# ORAO2007.net
KiCad netlist of a schematic drawn in EAGLE
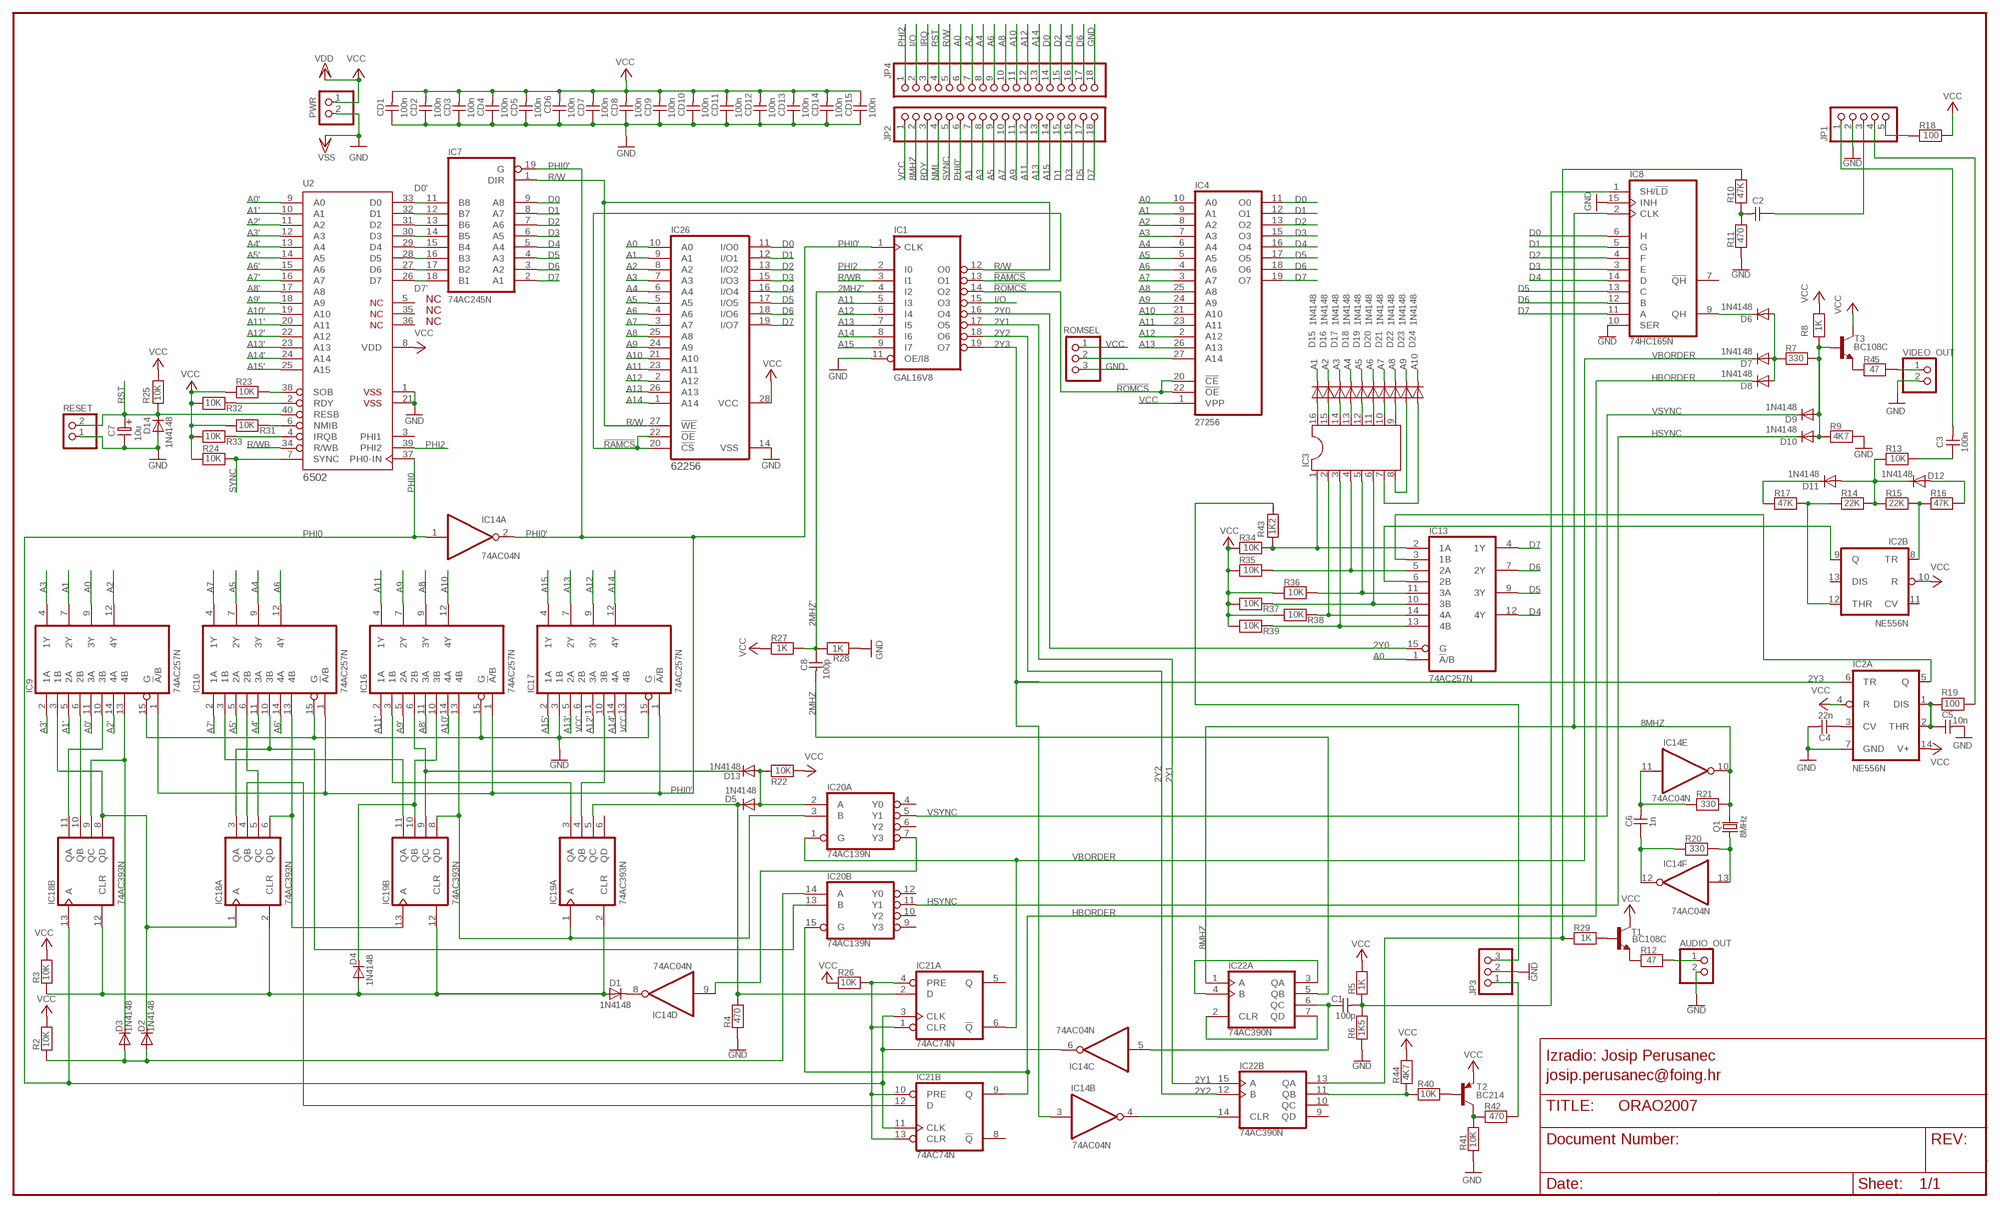
[diagram p0: schematic, sheet 1]

(export (version "E")
  (design (tool "Eeschema 10.0.6"))
  (components
    (comp (ref "AUDIO_OUT")
      (value "PINHD-1X2")
      (footprint "eagle-import:1X02")
      (libsource (lib "eagle-import") (part "PINHD-1X2"))
    )
    (comp (ref "C1")
      (value "100p")
      (footprint "eagle-import:C-5")
      (libsource (lib "eagle-import") (part "CAPNP-5"))
    )
    (comp (ref "C2")
      (value "CAPNP-5")
      (footprint "eagle-import:C-5")
      (libsource (lib "eagle-import") (part "CAPNP-5"))
    )
    (comp (ref "C3")
      (value "100n")
      (footprint "eagle-import:C-5")
      (libsource (lib "eagle-import") (part "CAPNP-5"))
    )
    (comp (ref "C4")
      (value "22n")
      (footprint "eagle-import:C-5")
      (libsource (lib "eagle-import") (part "CAPNP-5"))
    )
    (comp (ref "C5")
      (value "10n")
      (footprint "eagle-import:C-5")
      (libsource (lib "eagle-import") (part "CAPNP-5"))
    )
    (comp (ref "C6")
      (value "1n")
      (footprint "eagle-import:C-5")
      (libsource (lib "eagle-import") (part "CAPNP-5"))
    )
    (comp (ref "C7")
      (value "10u")
      (footprint "eagle-import:ES-2,5L")
      (libsource (lib "eagle-import") (part "ELC-2,5L"))
    )
    (comp (ref "C8")
      (value "100p")
      (footprint "eagle-import:C-5")
      (libsource (lib "eagle-import") (part "CAPNP-5"))
    )
    (comp (ref "CD1")
      (value "100n")
      (footprint "eagle-import:C-5")
      (libsource (lib "eagle-import") (part "CAPNP-5"))
    )
    (comp (ref "CD2")
      (value "100n")
      (footprint "eagle-import:C-5")
      (libsource (lib "eagle-import") (part "CAPNP-5"))
    )
    (comp (ref "CD3")
      (value "100n")
      (footprint "eagle-import:C-5")
      (libsource (lib "eagle-import") (part "CAPNP-5"))
    )
    (comp (ref "CD4")
      (value "100n")
      (footprint "eagle-import:C-5")
      (libsource (lib "eagle-import") (part "CAPNP-5"))
    )
    (comp (ref "CD5")
      (value "100n")
      (footprint "eagle-import:C-5")
      (libsource (lib "eagle-import") (part "CAPNP-5"))
    )
    (comp (ref "CD6")
      (value "100n")
      (footprint "eagle-import:C-5")
      (libsource (lib "eagle-import") (part "CAPNP-5"))
    )
    (comp (ref "CD7")
      (value "100n")
      (footprint "eagle-import:C-5")
      (libsource (lib "eagle-import") (part "CAPNP-5"))
    )
    (comp (ref "CD8")
      (value "100n")
      (footprint "eagle-import:C-5")
      (libsource (lib "eagle-import") (part "CAPNP-5"))
    )
    (comp (ref "CD9")
      (value "100n")
      (footprint "eagle-import:C-5")
      (libsource (lib "eagle-import") (part "CAPNP-5"))
    )
    (comp (ref "CD10")
      (value "100n")
      (footprint "eagle-import:C-5")
      (libsource (lib "eagle-import") (part "CAPNP-5"))
    )
    (comp (ref "CD11")
      (value "100n")
      (footprint "eagle-import:C-5")
      (libsource (lib "eagle-import") (part "CAPNP-5"))
    )
    (comp (ref "CD12")
      (value "100n")
      (footprint "eagle-import:C-5")
      (libsource (lib "eagle-import") (part "CAPNP-5"))
    )
    (comp (ref "CD13")
      (value "100n")
      (footprint "eagle-import:C-5")
      (libsource (lib "eagle-import") (part "CAPNP-5"))
    )
    (comp (ref "CD14")
      (value "100n")
      (footprint "eagle-import:C-5")
      (libsource (lib "eagle-import") (part "CAPNP-5"))
    )
    (comp (ref "CD15")
      (value "100n")
      (footprint "eagle-import:C-5")
      (libsource (lib "eagle-import") (part "CAPNP-5"))
    )
    (comp (ref "D1")
      (value "1N4148")
      (footprint "eagle-import:DO35-10")
      (libsource (lib "eagle-import") (part "1N4148"))
    )
    (comp (ref "D2")
      (value "1N4148")
      (footprint "eagle-import:DO35-10")
      (libsource (lib "eagle-import") (part "1N4148"))
    )
    (comp (ref "D3")
      (value "1N4148")
      (footprint "eagle-import:DO35-10")
      (libsource (lib "eagle-import") (part "1N4148"))
    )
    (comp (ref "D4")
      (value "1N4148")
      (footprint "eagle-import:DO35-10")
      (libsource (lib "eagle-import") (part "1N4148"))
    )
    (comp (ref "D5")
      (value "1N4148")
      (footprint "eagle-import:DO35-10")
      (libsource (lib "eagle-import") (part "1N4148"))
    )
    (comp (ref "D6")
      (value "1N4148")
      (footprint "eagle-import:DO35-10")
      (libsource (lib "eagle-import") (part "1N4148"))
    )
    (comp (ref "D7")
      (value "1N4148")
      (footprint "eagle-import:DO35-10")
      (libsource (lib "eagle-import") (part "1N4148"))
    )
    (comp (ref "D8")
      (value "1N4148")
      (footprint "eagle-import:DO35-10")
      (libsource (lib "eagle-import") (part "1N4148"))
    )
    (comp (ref "D9")
      (value "1N4148")
      (footprint "eagle-import:DO35-10")
      (libsource (lib "eagle-import") (part "1N4148"))
    )
    (comp (ref "D10")
      (value "1N4148")
      (footprint "eagle-import:DO35-10")
      (libsource (lib "eagle-import") (part "1N4148"))
    )
    (comp (ref "D11")
      (value "1N4148")
      (footprint "eagle-import:DO35-10")
      (libsource (lib "eagle-import") (part "1N4148"))
    )
    (comp (ref "D12")
      (value "1N4148")
      (footprint "eagle-import:DO35-10")
      (libsource (lib "eagle-import") (part "1N4148"))
    )
    (comp (ref "D13")
      (value "1N4148")
      (footprint "eagle-import:DO35-10")
      (libsource (lib "eagle-import") (part "1N4148"))
    )
    (comp (ref "D14")
      (value "1N4148")
      (footprint "eagle-import:DO35-10")
      (libsource (lib "eagle-import") (part "1N4148"))
    )
    (comp (ref "D15")
      (value "1N4148")
      (footprint "eagle-import:DO35-10")
      (libsource (lib "eagle-import") (part "1N4148"))
    )
    (comp (ref "D16")
      (value "1N4148")
      (footprint "eagle-import:DO35-10")
      (libsource (lib "eagle-import") (part "1N4148"))
    )
    (comp (ref "D17")
      (value "1N4148")
      (footprint "eagle-import:DO35-10")
      (libsource (lib "eagle-import") (part "1N4148"))
    )
    (comp (ref "D18")
      (value "1N4148")
      (footprint "eagle-import:DO35-10")
      (libsource (lib "eagle-import") (part "1N4148"))
    )
    (comp (ref "D19")
      (value "1N4148")
      (footprint "eagle-import:DO35-10")
      (libsource (lib "eagle-import") (part "1N4148"))
    )
    (comp (ref "D20")
      (value "1N4148")
      (footprint "eagle-import:DO35-10")
      (libsource (lib "eagle-import") (part "1N4148"))
    )
    (comp (ref "D21")
      (value "1N4148")
      (footprint "eagle-import:DO35-10")
      (libsource (lib "eagle-import") (part "1N4148"))
    )
    (comp (ref "D22")
      (value "1N4148")
      (footprint "eagle-import:DO35-10")
      (libsource (lib "eagle-import") (part "1N4148"))
    )
    (comp (ref "D23")
      (value "1N4148")
      (footprint "eagle-import:DO35-10")
      (libsource (lib "eagle-import") (part "1N4148"))
    )
    (comp (ref "D24")
      (value "1N4148")
      (footprint "eagle-import:DO35-10")
      (libsource (lib "eagle-import") (part "1N4148"))
    )
    (comp (ref "IC1")
      (value "GAL16V8")
      (footprint "eagle-import:DIL20")
      (libsource (lib "eagle-import") (part "16V8"))
    )
    (comp (ref "IC2")
      (value "NE556N")
      (footprint "eagle-import:DIL14")
      (libsource (lib "eagle-import") (part "556NNE"))
    )
    (comp (ref "IC3")
      (value "DIL16S")
      (footprint "eagle-import:SOCKED-16")
      (libsource (lib "eagle-import") (part "DIL16S"))
    )
    (comp (ref "IC4")
      (value "27256")
      (footprint "eagle-import:DIL28")
      (libsource (lib "eagle-import") (part "27256"))
    )
    (comp (ref "IC7")
      (value "74AC245N")
      (footprint "eagle-import:DIL20")
      (libsource (lib "eagle-import") (part "74245NAC"))
    )
    (comp (ref "IC8")
      (value "74HC165N")
      (footprint "eagle-import:DIL16")
      (libsource (lib "eagle-import") (part "74165NHC"))
    )
    (comp (ref "IC9")
      (value "74AC257N")
      (footprint "eagle-import:DIL16")
      (libsource (lib "eagle-import") (part "74257NAC"))
    )
    (comp (ref "IC10")
      (value "74AC257N")
      (footprint "eagle-import:DIL16")
      (libsource (lib "eagle-import") (part "74257NAC"))
    )
    (comp (ref "IC13")
      (value "74AC257N")
      (footprint "eagle-import:DIL16")
      (libsource (lib "eagle-import") (part "74257NAC"))
    )
    (comp (ref "IC14")
      (value "74AC04N")
      (footprint "eagle-import:DIL14")
      (libsource (lib "eagle-import") (part "7404NAC"))
    )
    (comp (ref "IC16")
      (value "74AC257N")
      (footprint "eagle-import:DIL16")
      (libsource (lib "eagle-import") (part "74257NAC"))
    )
    (comp (ref "IC17")
      (value "74AC257N")
      (footprint "eagle-import:DIL16")
      (libsource (lib "eagle-import") (part "74257NAC"))
    )
    (comp (ref "IC18")
      (value "74AC393N")
      (footprint "eagle-import:DIL14")
      (libsource (lib "eagle-import") (part "74393NAC"))
    )
    (comp (ref "IC19")
      (value "74AC393N")
      (footprint "eagle-import:DIL14")
      (libsource (lib "eagle-import") (part "74393NAC"))
    )
    (comp (ref "IC20")
      (value "74AC139N")
      (footprint "eagle-import:DIL16")
      (libsource (lib "eagle-import") (part "74139NAC"))
    )
    (comp (ref "IC21")
      (value "74AC74N")
      (footprint "eagle-import:DIL14")
      (libsource (lib "eagle-import") (part "7474NAC"))
    )
    (comp (ref "IC22")
      (value "74AC390N")
      (footprint "eagle-import:DIL16")
      (libsource (lib "eagle-import") (part "74390NAC"))
    )
    (comp (ref "IC26")
      (value "62256")
      (footprint "eagle-import:DIL28-6")
      (libsource (lib "eagle-import") (part "62256P"))
    )
    (comp (ref "JP1")
      (value "PINHD-1X5")
      (footprint "eagle-import:1X05")
      (libsource (lib "eagle-import") (part "PINHD-1X5"))
    )
    (comp (ref "JP2")
      (value "PINHD-1X18")
      (footprint "eagle-import:1X18")
      (libsource (lib "eagle-import") (part "PINHD-1X18"))
    )
    (comp (ref "JP3")
      (value "PINHD-1X3")
      (footprint "eagle-import:1X03")
      (libsource (lib "eagle-import") (part "PINHD-1X3"))
    )
    (comp (ref "JP4")
      (value "PINHD-1X18")
      (footprint "eagle-import:1X18")
      (libsource (lib "eagle-import") (part "PINHD-1X18"))
    )
    (comp (ref "PWR")
      (value "PINHD-1X2")
      (footprint "eagle-import:1X02")
      (libsource (lib "eagle-import") (part "PINHD-1X2"))
    )
    (comp (ref "Q1")
      (value "8MHz")
      (footprint "eagle-import:HC49_S")
      (libsource (lib "eagle-import") (part "CRYTALHC49S"))
    )
    (comp (ref "R2")
      (value "10K")
      (footprint "eagle-import:R-7,5")
      (libsource (lib "eagle-import") (part "RESEU-7,5"))
    )
    (comp (ref "R3")
      (value "10K")
      (footprint "eagle-import:R-7,5")
      (libsource (lib "eagle-import") (part "RESEU-7,5"))
    )
    (comp (ref "R4")
      (value "470")
      (footprint "eagle-import:R-7,5")
      (libsource (lib "eagle-import") (part "RESEU-7,5"))
    )
    (comp (ref "R5")
      (value "1K")
      (footprint "eagle-import:R-7,5")
      (libsource (lib "eagle-import") (part "RESEU-7,5"))
    )
    (comp (ref "R6")
      (value "1K5")
      (footprint "eagle-import:R-7,5")
      (libsource (lib "eagle-import") (part "RESEU-7,5"))
    )
    (comp (ref "R7")
      (value "330")
      (footprint "eagle-import:R-7,5")
      (libsource (lib "eagle-import") (part "RESEU-7,5"))
    )
    (comp (ref "R8")
      (value "1K")
      (footprint "eagle-import:R-7,5")
      (libsource (lib "eagle-import") (part "RESEU-7,5"))
    )
    (comp (ref "R9")
      (value "4K7")
      (footprint "eagle-import:R-7,5")
      (libsource (lib "eagle-import") (part "RESEU-7,5"))
    )
    (comp (ref "R10")
      (value "47K")
      (footprint "eagle-import:R-7,5")
      (libsource (lib "eagle-import") (part "RESEU-7,5"))
    )
    (comp (ref "R11")
      (value "470")
      (footprint "eagle-import:R-7,5")
      (libsource (lib "eagle-import") (part "RESEU-7,5"))
    )
    (comp (ref "R12")
      (value "47")
      (footprint "eagle-import:R-7,5")
      (libsource (lib "eagle-import") (part "RESEU-7,5"))
    )
    (comp (ref "R13")
      (value "10K")
      (footprint "eagle-import:R-7,5")
      (libsource (lib "eagle-import") (part "RESEU-7,5"))
    )
    (comp (ref "R14")
      (value "22K")
      (footprint "eagle-import:R-7,5")
      (libsource (lib "eagle-import") (part "RESEU-7,5"))
    )
    (comp (ref "R15")
      (value "22K")
      (footprint "eagle-import:R-7,5")
      (libsource (lib "eagle-import") (part "RESEU-7,5"))
    )
    (comp (ref "R16")
      (value "47K")
      (footprint "eagle-import:R-7,5")
      (libsource (lib "eagle-import") (part "RESEU-7,5"))
    )
    (comp (ref "R17")
      (value "47K")
      (footprint "eagle-import:R-7,5")
      (libsource (lib "eagle-import") (part "RESEU-7,5"))
    )
    (comp (ref "R18")
      (value "100")
      (footprint "eagle-import:R-7,5")
      (libsource (lib "eagle-import") (part "RESEU-7,5"))
    )
    (comp (ref "R19")
      (value "100")
      (footprint "eagle-import:R-7,5")
      (libsource (lib "eagle-import") (part "RESEU-7,5"))
    )
    (comp (ref "R20")
      (value "330")
      (footprint "eagle-import:R-7,5")
      (libsource (lib "eagle-import") (part "RESEU-7,5"))
    )
    (comp (ref "R21")
      (value "330")
      (footprint "eagle-import:R-7,5")
      (libsource (lib "eagle-import") (part "RESEU-7,5"))
    )
    (comp (ref "R22")
      (value "10K")
      (footprint "eagle-import:R-7,5")
      (libsource (lib "eagle-import") (part "RESEU-7,5"))
    )
    (comp (ref "R23")
      (value "10K")
      (footprint "eagle-import:R-7,5")
      (libsource (lib "eagle-import") (part "RESEU-7,5"))
    )
    (comp (ref "R24")
      (value "10K")
      (footprint "eagle-import:R-7,5")
      (libsource (lib "eagle-import") (part "RESEU-7,5"))
    )
    (comp (ref "R25")
      (value "10K")
      (footprint "eagle-import:R-7,5")
      (libsource (lib "eagle-import") (part "RESEU-7,5"))
    )
    (comp (ref "R26")
      (value "10K")
      (footprint "eagle-import:R-7,5")
      (libsource (lib "eagle-import") (part "RESEU-7,5"))
    )
    (comp (ref "R27")
      (value "1K")
      (footprint "eagle-import:R-7,5")
      (libsource (lib "eagle-import") (part "RESEU-7,5"))
    )
    (comp (ref "R28")
      (value "1K")
      (footprint "eagle-import:R-7,5")
      (libsource (lib "eagle-import") (part "RESEU-7,5"))
    )
    (comp (ref "R29")
      (value "1K")
      (footprint "eagle-import:R-7,5")
      (libsource (lib "eagle-import") (part "RESEU-7,5"))
    )
    (comp (ref "R31")
      (value "10K")
      (footprint "eagle-import:R-7,5")
      (libsource (lib "eagle-import") (part "RESEU-7,5"))
    )
    (comp (ref "R32")
      (value "10K")
      (footprint "eagle-import:R-7,5")
      (libsource (lib "eagle-import") (part "RESEU-7,5"))
    )
    (comp (ref "R33")
      (value "10K")
      (footprint "eagle-import:R-7,5")
      (libsource (lib "eagle-import") (part "RESEU-7,5"))
    )
    (comp (ref "R34")
      (value "10K")
      (footprint "eagle-import:R-7,5")
      (libsource (lib "eagle-import") (part "RESEU-7,5"))
    )
    (comp (ref "R35")
      (value "10K")
      (footprint "eagle-import:R-7,5")
      (libsource (lib "eagle-import") (part "RESEU-7,5"))
    )
    (comp (ref "R36")
      (value "10K")
      (footprint "eagle-import:R-7,5")
      (libsource (lib "eagle-import") (part "RESEU-7,5"))
    )
    (comp (ref "R37")
      (value "10K")
      (footprint "eagle-import:R-7,5")
      (libsource (lib "eagle-import") (part "RESEU-7,5"))
    )
    (comp (ref "R38")
      (value "10K")
      (footprint "eagle-import:R-7,5")
      (libsource (lib "eagle-import") (part "RESEU-7,5"))
    )
    (comp (ref "R39")
      (value "10K")
      (footprint "eagle-import:R-7,5")
      (libsource (lib "eagle-import") (part "RESEU-7,5"))
    )
    (comp (ref "R40")
      (value "10K")
      (footprint "eagle-import:R-7,5")
      (libsource (lib "eagle-import") (part "RESEU-7,5"))
    )
    (comp (ref "R41")
      (value "10K")
      (footprint "eagle-import:R-7,5")
      (libsource (lib "eagle-import") (part "RESEU-7,5"))
    )
    (comp (ref "R42")
      (value "470")
      (footprint "eagle-import:R-7,5")
      (libsource (lib "eagle-import") (part "RESEU-7,5"))
    )
    (comp (ref "R43")
      (value "1K2")
      (footprint "eagle-import:R-7,5")
      (libsource (lib "eagle-import") (part "RESEU-7,5"))
    )
    (comp (ref "R44")
      (value "4K7")
      (footprint "eagle-import:R-7,5")
      (libsource (lib "eagle-import") (part "RESEU-7,5"))
    )
    (comp (ref "R45")
      (value "47")
      (footprint "eagle-import:R-7,5")
      (libsource (lib "eagle-import") (part "RESEU-7,5"))
    )
    (comp (ref "RESET")
      (value "PINHD-1X2")
      (footprint "eagle-import:1X02")
      (libsource (lib "eagle-import") (part "PINHD-1X2"))
    )
    (comp (ref "ROMSEL")
      (value "PINHD-1X3")
      (footprint "eagle-import:1X03")
      (libsource (lib "eagle-import") (part "PINHD-1X3"))
    )
    (comp (ref "T1")
      (value "BC108C")
      (footprint "eagle-import:TO18")
      (libsource (lib "eagle-import") (part "BC108C"))
    )
    (comp (ref "T2")
      (value "BC214")
      (footprint "eagle-import:TO92")
      (libsource (lib "eagle-import") (part "BC214"))
    )
    (comp (ref "T3")
      (value "BC108C")
      (footprint "eagle-import:TO18")
      (libsource (lib "eagle-import") (part "BC108C"))
    )
    (comp (ref "U2")
      (value "6502")
      (footprint "eagle-import:DIP-40")
      (libsource (lib "eagle-import") (part "G65SC02P"))
    )
    (comp (ref "VIDEO_OUT")
      (value "PINHD-1X2")
      (footprint "eagle-import:1X02")
      (libsource (lib "eagle-import") (part "PINHD-1X2"))
    )
  )
  (nets
    (net (code "1") (name "/2MHZ") (class "Default")
      (node (ref "C8") (pin "2") (pinfunction "2_2") (pintype "passive"))
      (node (ref "IC22") (pin "5") (pinfunction "QB_5") (pintype "output"))
    )
    (net (code "2") (name "/2MHZ'") (class "Default")
      (node (ref "C8") (pin "1") (pinfunction "1_1") (pintype "passive"))
      (node (ref "IC1") (pin "4") (pinfunction "I2_4") (pintype "input"))
      (node (ref "R27") (pin "1") (pinfunction "1_1") (pintype "passive"))
      (node (ref "R28") (pin "2") (pinfunction "2_2") (pintype "passive"))
    )
    (net (code "3") (name "/2Y0") (class "Default")
      (node (ref "IC1") (pin "16") (pinfunction "O4_16") (pintype "bidirectional"))
      (node (ref "IC13") (pin "15") (pinfunction "G_15") (pintype "input"))
    )
    (net (code "4") (name "/2Y1") (class "Default")
      (node (ref "IC1") (pin "17") (pinfunction "O5_17") (pintype "bidirectional"))
      (node (ref "IC22") (pin "15") (pinfunction "A_15") (pintype "input"))
    )
    (net (code "5") (name "/2Y2") (class "Default")
      (node (ref "IC1") (pin "18") (pinfunction "O6_18") (pintype "bidirectional"))
      (node (ref "IC22") (pin "12") (pinfunction "B_12") (pintype "input"))
    )
    (net (code "6") (name "/2Y3") (class "Default")
      (node (ref "IC1") (pin "19") (pinfunction "O7_19") (pintype "bidirectional"))
      (node (ref "IC14") (pin "3") (pinfunction "I_3") (pintype "input"))
      (node (ref "IC2") (pin "6") (pinfunction "TR_6") (pintype "input"))
    )
    (net (code "7") (name "/8MHZ") (class "Default")
      (node (ref "IC14") (pin "10") (pinfunction "O_10") (pintype "output"))
      (node (ref "IC22") (pin "1") (pinfunction "A_1") (pintype "input"))
      (node (ref "IC8") (pin "2") (pinfunction "CLK_2") (pintype "input"))
      (node (ref "JP2") (pin "2") (pinfunction "2_2") (pintype "passive"))
      (node (ref "Q1") (pin "2") (pinfunction "2_2") (pintype "passive"))
      (node (ref "R21") (pin "2") (pinfunction "2_2") (pintype "passive"))
    )
    (net (code "8") (name "/A0") (class "Default")
      (node (ref "IC13") (pin "1") (pinfunction "~{A}/B_1") (pintype "input"))
      (node (ref "IC26") (pin "10") (pinfunction "A0_10") (pintype "input"))
      (node (ref "IC4") (pin "10") (pinfunction "A0_10") (pintype "input"))
      (node (ref "IC9") (pin "9") (pinfunction "3Y_9") (pintype "tri_state"))
      (node (ref "JP4") (pin "6") (pinfunction "6_6") (pintype "passive"))
    )
    (net (code "9") (name "/A0'") (class "Default")
      (node (ref "IC9") (pin "11") (pinfunction "3A_11") (pintype "input"))
      (node (ref "U2") (pin "9") (pinfunction "A0_9") (pintype "bidirectional"))
    )
    (net (code "10") (name "/A1") (class "Default")
      (node (ref "D15") (pin "C") (pinfunction "C_C") (pintype "passive"))
      (node (ref "IC26") (pin "9") (pinfunction "A1_9") (pintype "input"))
      (node (ref "IC4") (pin "9") (pinfunction "A1_9") (pintype "input"))
      (node (ref "IC9") (pin "7") (pinfunction "2Y_7") (pintype "tri_state"))
      (node (ref "JP2") (pin "7") (pinfunction "7_7") (pintype "passive"))
    )
    (net (code "11") (name "/A1'") (class "Default")
      (node (ref "IC9") (pin "5") (pinfunction "2A_5") (pintype "input"))
      (node (ref "U2") (pin "10") (pinfunction "A1_10") (pintype "bidirectional"))
    )
    (net (code "12") (name "/A2") (class "Default")
      (node (ref "D16") (pin "C") (pinfunction "C_C") (pintype "passive"))
      (node (ref "IC26") (pin "8") (pinfunction "A2_8") (pintype "input"))
      (node (ref "IC4") (pin "8") (pinfunction "A2_8") (pintype "input"))
      (node (ref "IC9") (pin "12") (pinfunction "4Y_12") (pintype "tri_state"))
      (node (ref "JP4") (pin "7") (pinfunction "7_7") (pintype "passive"))
    )
    (net (code "13") (name "/A2'") (class "Default")
      (node (ref "IC9") (pin "14") (pinfunction "4A_14") (pintype "input"))
      (node (ref "U2") (pin "11") (pinfunction "A2_11") (pintype "bidirectional"))
    )
    (net (code "14") (name "/A3") (class "Default")
      (node (ref "D17") (pin "C") (pinfunction "C_C") (pintype "passive"))
      (node (ref "IC26") (pin "7") (pinfunction "A3_7") (pintype "input"))
      (node (ref "IC4") (pin "7") (pinfunction "A3_7") (pintype "input"))
      (node (ref "IC9") (pin "4") (pinfunction "1Y_4") (pintype "tri_state"))
      (node (ref "JP2") (pin "8") (pinfunction "8_8") (pintype "passive"))
    )
    (net (code "15") (name "/A3'") (class "Default")
      (node (ref "IC9") (pin "2") (pinfunction "1A_2") (pintype "input"))
      (node (ref "U2") (pin "12") (pinfunction "A3_12") (pintype "bidirectional"))
    )
    (net (code "16") (name "/A4") (class "Default")
      (node (ref "D18") (pin "C") (pinfunction "C_C") (pintype "passive"))
      (node (ref "IC10") (pin "9") (pinfunction "3Y_9") (pintype "tri_state"))
      (node (ref "IC26") (pin "6") (pinfunction "A4_6") (pintype "input"))
      (node (ref "IC4") (pin "6") (pinfunction "A4_6") (pintype "input"))
      (node (ref "JP4") (pin "8") (pinfunction "8_8") (pintype "passive"))
    )
    (net (code "17") (name "/A4'") (class "Default")
      (node (ref "IC10") (pin "11") (pinfunction "3A_11") (pintype "input"))
      (node (ref "U2") (pin "13") (pinfunction "A4_13") (pintype "bidirectional"))
    )
    (net (code "18") (name "/A5") (class "Default")
      (node (ref "D19") (pin "C") (pinfunction "C_C") (pintype "passive"))
      (node (ref "IC10") (pin "7") (pinfunction "2Y_7") (pintype "tri_state"))
      (node (ref "IC26") (pin "5") (pinfunction "A5_5") (pintype "input"))
      (node (ref "IC4") (pin "5") (pinfunction "A5_5") (pintype "input"))
      (node (ref "JP2") (pin "9") (pinfunction "9_9") (pintype "passive"))
    )
    (net (code "19") (name "/A5'") (class "Default")
      (node (ref "IC10") (pin "5") (pinfunction "2A_5") (pintype "input"))
      (node (ref "U2") (pin "14") (pinfunction "A5_14") (pintype "bidirectional"))
    )
    (net (code "20") (name "/A6") (class "Default")
      (node (ref "D20") (pin "C") (pinfunction "C_C") (pintype "passive"))
      (node (ref "IC10") (pin "12") (pinfunction "4Y_12") (pintype "tri_state"))
      (node (ref "IC26") (pin "4") (pinfunction "A6_4") (pintype "input"))
      (node (ref "IC4") (pin "4") (pinfunction "A6_4") (pintype "input"))
      (node (ref "JP4") (pin "9") (pinfunction "9_9") (pintype "passive"))
    )
    (net (code "21") (name "/A6'") (class "Default")
      (node (ref "IC10") (pin "14") (pinfunction "4A_14") (pintype "input"))
      (node (ref "U2") (pin "15") (pinfunction "A6_15") (pintype "bidirectional"))
    )
    (net (code "22") (name "/A7") (class "Default")
      (node (ref "D21") (pin "C") (pinfunction "C_C") (pintype "passive"))
      (node (ref "IC10") (pin "4") (pinfunction "1Y_4") (pintype "tri_state"))
      (node (ref "IC26") (pin "3") (pinfunction "A7_3") (pintype "input"))
      (node (ref "IC4") (pin "3") (pinfunction "A7_3") (pintype "input"))
      (node (ref "JP2") (pin "10") (pinfunction "10_10") (pintype "passive"))
    )
    (net (code "23") (name "/A7'") (class "Default")
      (node (ref "IC10") (pin "2") (pinfunction "1A_2") (pintype "input"))
      (node (ref "U2") (pin "16") (pinfunction "A7_16") (pintype "bidirectional"))
    )
    (net (code "24") (name "/A8") (class "Default")
      (node (ref "D22") (pin "C") (pinfunction "C_C") (pintype "passive"))
      (node (ref "IC16") (pin "9") (pinfunction "3Y_9") (pintype "tri_state"))
      (node (ref "IC26") (pin "25") (pinfunction "A8_25") (pintype "input"))
      (node (ref "IC4") (pin "25") (pinfunction "A8_25") (pintype "input"))
      (node (ref "JP4") (pin "10") (pinfunction "10_10") (pintype "passive"))
    )
    (net (code "25") (name "/A8'") (class "Default")
      (node (ref "IC16") (pin "11") (pinfunction "3A_11") (pintype "input"))
      (node (ref "U2") (pin "17") (pinfunction "A8_17") (pintype "bidirectional"))
    )
    (net (code "26") (name "/A9") (class "Default")
      (node (ref "D23") (pin "C") (pinfunction "C_C") (pintype "passive"))
      (node (ref "IC16") (pin "7") (pinfunction "2Y_7") (pintype "tri_state"))
      (node (ref "IC26") (pin "24") (pinfunction "A9_24") (pintype "input"))
      (node (ref "IC4") (pin "24") (pinfunction "A9_24") (pintype "input"))
      (node (ref "JP2") (pin "11") (pinfunction "11_11") (pintype "passive"))
    )
    (net (code "27") (name "/A9'") (class "Default")
      (node (ref "IC16") (pin "5") (pinfunction "2A_5") (pintype "input"))
      (node (ref "U2") (pin "18") (pinfunction "A9_18") (pintype "bidirectional"))
    )
    (net (code "28") (name "/A10") (class "Default")
      (node (ref "D24") (pin "C") (pinfunction "C_C") (pintype "passive"))
      (node (ref "IC16") (pin "12") (pinfunction "4Y_12") (pintype "tri_state"))
      (node (ref "IC26") (pin "21") (pinfunction "A10_21") (pintype "input"))
      (node (ref "IC4") (pin "21") (pinfunction "A10_21") (pintype "input"))
      (node (ref "JP4") (pin "11") (pinfunction "11_11") (pintype "passive"))
    )
    (net (code "29") (name "/A10'") (class "Default")
      (node (ref "IC16") (pin "14") (pinfunction "4A_14") (pintype "input"))
      (node (ref "U2") (pin "19") (pinfunction "A10_19") (pintype "bidirectional"))
    )
    (net (code "30") (name "/A11") (class "Default")
      (node (ref "IC1") (pin "5") (pinfunction "I3_5") (pintype "input"))
      (node (ref "IC16") (pin "4") (pinfunction "1Y_4") (pintype "tri_state"))
      (node (ref "IC26") (pin "23") (pinfunction "A11_23") (pintype "input"))
      (node (ref "IC4") (pin "23") (pinfunction "A11_23") (pintype "input"))
      (node (ref "JP2") (pin "12") (pinfunction "12_12") (pintype "passive"))
    )
    (net (code "31") (name "/A11'") (class "Default")
      (node (ref "IC16") (pin "2") (pinfunction "1A_2") (pintype "input"))
      (node (ref "U2") (pin "20") (pinfunction "A11_20") (pintype "bidirectional"))
    )
    (net (code "32") (name "/A12") (class "Default")
      (node (ref "IC1") (pin "6") (pinfunction "I4_6") (pintype "input"))
      (node (ref "IC17") (pin "9") (pinfunction "3Y_9") (pintype "tri_state"))
      (node (ref "IC26") (pin "2") (pinfunction "A12_2") (pintype "input"))
      (node (ref "IC4") (pin "2") (pinfunction "A12_2") (pintype "input"))
      (node (ref "JP4") (pin "12") (pinfunction "12_12") (pintype "passive"))
    )
    (net (code "33") (name "/A12'") (class "Default")
      (node (ref "IC17") (pin "11") (pinfunction "3A_11") (pintype "input"))
      (node (ref "U2") (pin "22") (pinfunction "A12_22") (pintype "bidirectional"))
    )
    (net (code "34") (name "/A13") (class "Default")
      (node (ref "IC1") (pin "7") (pinfunction "I5_7") (pintype "input"))
      (node (ref "IC17") (pin "7") (pinfunction "2Y_7") (pintype "tri_state"))
      (node (ref "IC26") (pin "26") (pinfunction "A13_26") (pintype "input"))
      (node (ref "IC4") (pin "26") (pinfunction "A13_26") (pintype "input"))
      (node (ref "JP2") (pin "13") (pinfunction "13_13") (pintype "passive"))
    )
    (net (code "35") (name "/A13'") (class "Default")
      (node (ref "IC17") (pin "5") (pinfunction "2A_5") (pintype "input"))
      (node (ref "U2") (pin "23") (pinfunction "A13_23") (pintype "bidirectional"))
    )
    (net (code "36") (name "/A14") (class "Default")
      (node (ref "IC1") (pin "8") (pinfunction "I6_8") (pintype "input"))
      (node (ref "IC17") (pin "12") (pinfunction "4Y_12") (pintype "tri_state"))
      (node (ref "IC26") (pin "1") (pinfunction "A14_1") (pintype "input"))
      (node (ref "JP4") (pin "13") (pinfunction "13_13") (pintype "passive"))
    )
    (net (code "37") (name "/A14'") (class "Default")
      (node (ref "IC17") (pin "14") (pinfunction "4A_14") (pintype "input"))
      (node (ref "U2") (pin "24") (pinfunction "A14_24") (pintype "bidirectional"))
    )
    (net (code "38") (name "/A15") (class "Default")
      (node (ref "IC1") (pin "9") (pinfunction "I7_9") (pintype "input"))
      (node (ref "IC17") (pin "4") (pinfunction "1Y_4") (pintype "tri_state"))
      (node (ref "JP2") (pin "14") (pinfunction "14_14") (pintype "passive"))
    )
    (net (code "39") (name "/A15'") (class "Default")
      (node (ref "IC17") (pin "2") (pinfunction "1A_2") (pintype "input"))
      (node (ref "U2") (pin "25") (pinfunction "A15_25") (pintype "bidirectional"))
    )
    (net (code "40") (name "/D0") (class "Default")
      (node (ref "IC26") (pin "11") (pinfunction "I/O0_11") (pintype "bidirectional"))
      (node (ref "IC4") (pin "11") (pinfunction "O0_11") (pintype "tri_state"))
      (node (ref "IC7") (pin "9") (pinfunction "A8_9") (pintype "bidirectional"))
      (node (ref "IC8") (pin "6") (pinfunction "H_6") (pintype "input"))
      (node (ref "JP4") (pin "14") (pinfunction "14_14") (pintype "passive"))
    )
    (net (code "41") (name "/D0'") (class "Default")
      (node (ref "IC7") (pin "11") (pinfunction "B8_11") (pintype "bidirectional"))
      (node (ref "U2") (pin "33") (pinfunction "D0_33") (pintype "bidirectional"))
    )
    (net (code "42") (name "/D1") (class "Default")
      (node (ref "IC26") (pin "12") (pinfunction "I/O1_12") (pintype "bidirectional"))
      (node (ref "IC4") (pin "12") (pinfunction "O1_12") (pintype "tri_state"))
      (node (ref "IC7") (pin "8") (pinfunction "A7_8") (pintype "bidirectional"))
      (node (ref "IC8") (pin "5") (pinfunction "G_5") (pintype "input"))
      (node (ref "JP2") (pin "15") (pinfunction "15_15") (pintype "passive"))
    )
    (net (code "43") (name "/D2") (class "Default")
      (node (ref "IC26") (pin "13") (pinfunction "I/O2_13") (pintype "bidirectional"))
      (node (ref "IC4") (pin "13") (pinfunction "O2_13") (pintype "tri_state"))
      (node (ref "IC7") (pin "7") (pinfunction "A6_7") (pintype "bidirectional"))
      (node (ref "IC8") (pin "4") (pinfunction "F_4") (pintype "input"))
      (node (ref "JP4") (pin "15") (pinfunction "15_15") (pintype "passive"))
    )
    (net (code "44") (name "/D3") (class "Default")
      (node (ref "IC26") (pin "15") (pinfunction "I/O3_15") (pintype "bidirectional"))
      (node (ref "IC4") (pin "15") (pinfunction "O3_15") (pintype "tri_state"))
      (node (ref "IC7") (pin "6") (pinfunction "A5_6") (pintype "bidirectional"))
      (node (ref "IC8") (pin "3") (pinfunction "E_3") (pintype "input"))
      (node (ref "JP2") (pin "16") (pinfunction "16_16") (pintype "passive"))
    )
    (net (code "45") (name "/D4") (class "Default")
      (node (ref "IC13") (pin "12") (pinfunction "4Y_12") (pintype "tri_state"))
      (node (ref "IC26") (pin "16") (pinfunction "I/O4_16") (pintype "bidirectional"))
      (node (ref "IC4") (pin "16") (pinfunction "O4_16") (pintype "tri_state"))
      (node (ref "IC7") (pin "5") (pinfunction "A4_5") (pintype "bidirectional"))
      (node (ref "IC8") (pin "14") (pinfunction "D_14") (pintype "input"))
      (node (ref "JP4") (pin "16") (pinfunction "16_16") (pintype "passive"))
    )
    (net (code "46") (name "/D5") (class "Default")
      (node (ref "IC13") (pin "9") (pinfunction "3Y_9") (pintype "tri_state"))
      (node (ref "IC26") (pin "17") (pinfunction "I/O5_17") (pintype "bidirectional"))
      (node (ref "IC4") (pin "17") (pinfunction "O5_17") (pintype "tri_state"))
      (node (ref "IC7") (pin "4") (pinfunction "A3_4") (pintype "bidirectional"))
      (node (ref "IC8") (pin "13") (pinfunction "C_13") (pintype "input"))
      (node (ref "JP2") (pin "17") (pinfunction "17_17") (pintype "passive"))
    )
    (net (code "47") (name "/D6") (class "Default")
      (node (ref "IC13") (pin "7") (pinfunction "2Y_7") (pintype "tri_state"))
      (node (ref "IC26") (pin "18") (pinfunction "I/O6_18") (pintype "bidirectional"))
      (node (ref "IC4") (pin "18") (pinfunction "O6_18") (pintype "tri_state"))
      (node (ref "IC7") (pin "3") (pinfunction "A2_3") (pintype "bidirectional"))
      (node (ref "IC8") (pin "12") (pinfunction "B_12") (pintype "input"))
      (node (ref "JP4") (pin "17") (pinfunction "17_17") (pintype "passive"))
    )
    (net (code "48") (name "/D7") (class "Default")
      (node (ref "IC13") (pin "4") (pinfunction "1Y_4") (pintype "tri_state"))
      (node (ref "IC26") (pin "19") (pinfunction "I/O7_19") (pintype "bidirectional"))
      (node (ref "IC4") (pin "19") (pinfunction "O7_19") (pintype "tri_state"))
      (node (ref "IC7") (pin "2") (pinfunction "A1_2") (pintype "bidirectional"))
      (node (ref "IC8") (pin "11") (pinfunction "A_11") (pintype "input"))
      (node (ref "JP2") (pin "18") (pinfunction "18_18") (pintype "passive"))
    )
    (net (code "49") (name "/D7'") (class "Default")
      (node (ref "IC7") (pin "18") (pinfunction "B1_18") (pintype "bidirectional"))
      (node (ref "U2") (pin "26") (pinfunction "D7_26") (pintype "bidirectional"))
    )
    (net (code "50") (name "/HBORDER") (class "Default")
      (node (ref "D8") (pin "C") (pinfunction "C_C") (pintype "passive"))
      (node (ref "IC20") (pin "15") (pinfunction "G_15") (pintype "input"))
      (node (ref "IC21") (pin "9") (pinfunction "Q_9") (pintype "output"))
    )
    (net (code "51") (name "/HSYNC") (class "Default")
      (node (ref "D10") (pin "C") (pinfunction "C_C") (pintype "passive"))
      (node (ref "IC20") (pin "11") (pinfunction "Y1_11") (pintype "output"))
    )
    (net (code "52") (name "/IRQ") (class "Default")
      (node (ref "JP4") (pin "3") (pinfunction "3_3") (pintype "passive"))
      (node (ref "R33") (pin "2") (pinfunction "2_2") (pintype "passive"))
      (node (ref "U2") (pin "4") (pinfunction "IRQB_4") (pintype "input"))
    )
    (net (code "53") (name "/I{slash}O") (class "Default")
      (node (ref "IC1") (pin "15") (pinfunction "O3_15") (pintype "bidirectional"))
      (node (ref "JP4") (pin "2") (pinfunction "2_2") (pintype "passive"))
    )
    (net (code "54") (name "/NMI") (class "Default")
      (node (ref "JP2") (pin "4") (pinfunction "4_4") (pintype "passive"))
      (node (ref "R31") (pin "2") (pinfunction "2_2") (pintype "passive"))
      (node (ref "U2") (pin "6") (pinfunction "NMIB_6") (pintype "input"))
    )
    (net (code "55") (name "/PHI0") (class "Default")
      (node (ref "IC14") (pin "1") (pinfunction "I_1") (pintype "input"))
      (node (ref "IC14") (pin "6") (pinfunction "O_6") (pintype "output"))
      (node (ref "IC18") (pin "13") (pinfunction "A_13") (pintype "input"))
      (node (ref "IC21") (pin "11") (pinfunction "CLK_11") (pintype "input"))
      (node (ref "IC21") (pin "3") (pinfunction "CLK_3") (pintype "input"))
      (node (ref "U2") (pin "37") (pinfunction "PH0-IN_37") (pintype "input"))
    )
    (net (code "56") (name "/PHI0'") (class "Default")
      (node (ref "IC1") (pin "1") (pinfunction "CLK_1") (pintype "input"))
      (node (ref "IC10") (pin "1") (pinfunction "~{A}/B_1") (pintype "input"))
      (node (ref "IC14") (pin "2") (pinfunction "O_2") (pintype "output"))
      (node (ref "IC16") (pin "1") (pinfunction "~{A}/B_1") (pintype "input"))
      (node (ref "IC17") (pin "1") (pinfunction "~{A}/B_1") (pintype "input"))
      (node (ref "IC7") (pin "19") (pinfunction "G_19") (pintype "input"))
      (node (ref "IC9") (pin "1") (pinfunction "~{A}/B_1") (pintype "input"))
      (node (ref "JP2") (pin "6") (pinfunction "6_6") (pintype "passive"))
    )
    (net (code "57") (name "/PHI2") (class "Default")
      (node (ref "IC1") (pin "2") (pinfunction "I0_2") (pintype "input"))
      (node (ref "JP4") (pin "1") (pinfunction "1_1") (pintype "passive"))
      (node (ref "U2") (pin "39") (pinfunction "PHI2_39") (pintype "output"))
    )
    (net (code "58") (name "/RDY") (class "Default")
      (node (ref "JP2") (pin "3") (pinfunction "3_3") (pintype "passive"))
      (node (ref "R32") (pin "2") (pinfunction "2_2") (pintype "passive"))
      (node (ref "U2") (pin "2") (pinfunction "RDY_2") (pintype "bidirectional"))
    )
    (net (code "59") (name "/RST") (class "Default")
      (node (ref "C7") (pin "1") (pinfunction "1_1") (pintype "passive"))
      (node (ref "D14") (pin "C") (pinfunction "C_C") (pintype "passive"))
      (node (ref "JP4") (pin "4") (pinfunction "4_4") (pintype "passive"))
      (node (ref "R25") (pin "1") (pinfunction "1_1") (pintype "passive"))
      (node (ref "RESET") (pin "2") (pinfunction "2_2") (pintype "passive"))
      (node (ref "U2") (pin "40") (pinfunction "RESB_40") (pintype "input"))
    )
    (net (code "60") (name "/R{slash}W") (class "Default")
      (node (ref "IC1") (pin "12") (pinfunction "O0_12") (pintype "bidirectional"))
      (node (ref "IC26") (pin "27") (pinfunction "~{WE}_27") (pintype "input"))
      (node (ref "IC7") (pin "1") (pinfunction "DIR_1") (pintype "input"))
      (node (ref "JP4") (pin "5") (pinfunction "5_5") (pintype "passive"))
    )
    (net (code "61") (name "/R{slash}WB") (class "Default")
      (node (ref "IC1") (pin "3") (pinfunction "I1_3") (pintype "input"))
      (node (ref "U2") (pin "34") (pinfunction "R/WB_34") (pintype "output"))
    )
    (net (code "62") (name "/SYNC") (class "Default")
      (node (ref "JP2") (pin "5") (pinfunction "5_5") (pintype "passive"))
      (node (ref "R24") (pin "2") (pinfunction "2_2") (pintype "passive"))
      (node (ref "U2") (pin "7") (pinfunction "SYNC_7") (pintype "output"))
    )
    (net (code "63") (name "/VBORDER") (class "Default")
      (node (ref "D7") (pin "C") (pinfunction "C_C") (pintype "passive"))
      (node (ref "IC20") (pin "1") (pinfunction "G_1") (pintype "input"))
      (node (ref "IC21") (pin "6") (pinfunction "~{Q}_6") (pintype "output"))
    )
    (net (code "64") (name "/VSYNC") (class "Default")
      (node (ref "D9") (pin "C") (pinfunction "C_C") (pintype "passive"))
      (node (ref "IC20") (pin "5") (pinfunction "Y1_5") (pintype "output"))
    )
    (net (code "65") (name "/~{RAMCS}") (class "Default")
      (node (ref "IC1") (pin "13") (pinfunction "O1_13") (pintype "bidirectional"))
      (node (ref "IC26") (pin "20") (pinfunction "~{CS}_20") (pintype "input"))
      (node (ref "IC26") (pin "22") (pinfunction "~{OE}_22") (pintype "input"))
    )
    (net (code "66") (name "/~{ROMCS}") (class "Default")
      (node (ref "IC1") (pin "14") (pinfunction "O2_14") (pintype "bidirectional"))
      (node (ref "IC4") (pin "20") (pinfunction "~{CE}_20") (pintype "input"))
      (node (ref "IC4") (pin "22") (pinfunction "~{OE}_22") (pintype "input"))
    )
    (net (code "67") (name "GND") (class "Default")
      (node (ref "AUDIO_OUT") (pin "2") (pinfunction "2_2") (pintype "passive"))
      (node (ref "C4") (pin "2") (pinfunction "2_2") (pintype "passive"))
      (node (ref "C5") (pin "2") (pinfunction "2_2") (pintype "passive"))
      (node (ref "C7") (pin "2") (pinfunction "2_2") (pintype "passive"))
      (node (ref "CD1") (pin "1") (pinfunction "1_1") (pintype "passive"))
      (node (ref "CD10") (pin "1") (pinfunction "1_1") (pintype "passive"))
      (node (ref "CD11") (pin "1") (pinfunction "1_1") (pintype "passive"))
      (node (ref "CD12") (pin "1") (pinfunction "1_1") (pintype "passive"))
      (node (ref "CD13") (pin "1") (pinfunction "1_1") (pintype "passive"))
      (node (ref "CD14") (pin "1") (pinfunction "1_1") (pintype "passive"))
      (node (ref "CD15") (pin "1") (pinfunction "1_1") (pintype "passive"))
      (node (ref "CD2") (pin "1") (pinfunction "1_1") (pintype "passive"))
      (node (ref "CD3") (pin "1") (pinfunction "1_1") (pintype "passive"))
      (node (ref "CD4") (pin "1") (pinfunction "1_1") (pintype "passive"))
      (node (ref "CD5") (pin "1") (pinfunction "1_1") (pintype "passive"))
      (node (ref "CD6") (pin "1") (pinfunction "1_1") (pintype "passive"))
      (node (ref "CD7") (pin "1") (pinfunction "1_1") (pintype "passive"))
      (node (ref "CD8") (pin "1") (pinfunction "1_1") (pintype "passive"))
      (node (ref "CD9") (pin "1") (pinfunction "1_1") (pintype "passive"))
      (node (ref "D14") (pin "A") (pinfunction "A_A") (pintype "passive"))
      (node (ref "IC1") (pin "11") (pinfunction "OE/I8_11") (pintype "input"))
      (node (ref "IC10") (pin "15") (pinfunction "G_15") (pintype "input"))
      (node (ref "IC16") (pin "15") (pinfunction "G_15") (pintype "input"))
      (node (ref "IC17") (pin "15") (pinfunction "G_15") (pintype "input"))
      (node (ref "IC17") (pin "3") (pinfunction "1B_3") (pintype "input"))
      (node (ref "IC2") (pin "7") (pinfunction "GND_7") (pintype "power_in"))
      (node (ref "IC26") (pin "14") (pinfunction "VSS_14") (pintype "power_in"))
      (node (ref "IC8") (pin "10") (pinfunction "SER_10") (pintype "input"))
      (node (ref "IC8") (pin "15") (pinfunction "INH_15") (pintype "input"))
      (node (ref "IC9") (pin "15") (pinfunction "G_15") (pintype "input"))
      (node (ref "JP1") (pin "2") (pinfunction "2_2") (pintype "passive"))
      (node (ref "JP3") (pin "2") (pinfunction "2_2") (pintype "passive"))
      (node (ref "JP4") (pin "18") (pinfunction "18_18") (pintype "passive"))
      (node (ref "PWR") (pin "2") (pinfunction "2_2") (pintype "passive"))
      (node (ref "R11") (pin "1") (pinfunction "1_1") (pintype "passive"))
      (node (ref "R28") (pin "1") (pinfunction "1_1") (pintype "passive"))
      (node (ref "R4") (pin "1") (pinfunction "1_1") (pintype "passive"))
      (node (ref "R41") (pin "2") (pinfunction "2_2") (pintype "passive"))
      (node (ref "R6") (pin "1") (pinfunction "1_1") (pintype "passive"))
      (node (ref "R9") (pin "2") (pinfunction "2_2") (pintype "passive"))
      (node (ref "RESET") (pin "1") (pinfunction "1_1") (pintype "passive"))
      (node (ref "ROMSEL") (pin "3") (pinfunction "3_3") (pintype "passive"))
      (node (ref "U2") (pin "1") (pinfunction "VSS$1_1") (pintype "power_in"))
      (node (ref "U2") (pin "21") (pinfunction "VSS$2_21") (pintype "power_in"))
      (node (ref "VIDEO_OUT") (pin "2") (pinfunction "2_2") (pintype "passive"))
    )
    (net (code "68") (name "Net-(AUDIO_OUT-Pad1)") (class "Default")
      (node (ref "AUDIO_OUT") (pin "1") (pinfunction "1_1") (pintype "passive"))
      (node (ref "R12") (pin "2") (pinfunction "2_2") (pintype "passive"))
    )
    (net (code "69") (name "Net-(C2-Pad1)") (class "Default")
      (node (ref "C2") (pin "1") (pinfunction "1_1") (pintype "passive"))
      (node (ref "JP1") (pin "3") (pinfunction "3_3") (pintype "passive"))
    )
    (net (code "70") (name "Net-(C2-Pad2)") (class "Default")
      (node (ref "C2") (pin "2") (pinfunction "2_2") (pintype "passive"))
      (node (ref "R10") (pin "2") (pinfunction "2_2") (pintype "passive"))
      (node (ref "R11") (pin "2") (pinfunction "2_2") (pintype "passive"))
    )
    (net (code "71") (name "Net-(C3-Pad1)") (class "Default")
      (node (ref "C3") (pin "1") (pinfunction "1_1") (pintype "passive"))
      (node (ref "R13") (pin "1") (pinfunction "1_1") (pintype "passive"))
    )
    (net (code "72") (name "Net-(C3-Pad2)") (class "Default")
      (node (ref "C3") (pin "2") (pinfunction "2_2") (pintype "passive"))
      (node (ref "JP1") (pin "1") (pinfunction "1_1") (pintype "passive"))
    )
    (net (code "73") (name "Net-(D6-PadA)") (class "Default")
      (node (ref "D6") (pin "A") (pinfunction "A_A") (pintype "passive"))
      (node (ref "D7") (pin "A") (pinfunction "A_A") (pintype "passive"))
      (node (ref "D8") (pin "A") (pinfunction "A_A") (pintype "passive"))
      (node (ref "R7") (pin "1") (pinfunction "1_1") (pintype "passive"))
    )
    (net (code "74") (name "Net-(D11-PadA)") (class "Default")
      (node (ref "D11") (pin "A") (pinfunction "A_A") (pintype "passive"))
      (node (ref "D12") (pin "C") (pinfunction "C_C") (pintype "passive"))
      (node (ref "R13") (pin "2") (pinfunction "2_2") (pintype "passive"))
      (node (ref "R14") (pin "2") (pinfunction "2_2") (pintype "passive"))
      (node (ref "R15") (pin "1") (pinfunction "1_1") (pintype "passive"))
    )
    (net (code "75") (name "Net-(D11-PadC)") (class "Default")
      (node (ref "D11") (pin "C") (pinfunction "C_C") (pintype "passive"))
      (node (ref "R17") (pin "1") (pinfunction "1_1") (pintype "passive"))
    )
    (net (code "76") (name "Net-(D12-PadA)") (class "Default")
      (node (ref "D12") (pin "A") (pinfunction "A_A") (pintype "passive"))
      (node (ref "R16") (pin "2") (pinfunction "2_2") (pintype "passive"))
    )
    (net (code "77") (name "Net-(D15-PadA)") (class "Default")
      (node (ref "D15") (pin "A") (pinfunction "A_A") (pintype "passive"))
      (node (ref "IC3") (pin "16") (pinfunction "16_16") (pintype "passive"))
    )
    (net (code "78") (name "Net-(D16-PadA)") (class "Default")
      (node (ref "D16") (pin "A") (pinfunction "A_A") (pintype "passive"))
      (node (ref "IC3") (pin "15") (pinfunction "15_15") (pintype "passive"))
    )
    (net (code "79") (name "Net-(D17-PadA)") (class "Default")
      (node (ref "D17") (pin "A") (pinfunction "A_A") (pintype "passive"))
      (node (ref "IC3") (pin "14") (pinfunction "14_14") (pintype "passive"))
    )
    (net (code "80") (name "Net-(D18-PadA)") (class "Default")
      (node (ref "D18") (pin "A") (pinfunction "A_A") (pintype "passive"))
      (node (ref "IC3") (pin "13") (pinfunction "13_13") (pintype "passive"))
    )
    (net (code "81") (name "Net-(D19-PadA)") (class "Default")
      (node (ref "D19") (pin "A") (pinfunction "A_A") (pintype "passive"))
      (node (ref "IC3") (pin "12") (pinfunction "12_12") (pintype "passive"))
    )
    (net (code "82") (name "Net-(D20-PadA)") (class "Default")
      (node (ref "D20") (pin "A") (pinfunction "A_A") (pintype "passive"))
      (node (ref "IC3") (pin "11") (pinfunction "11_11") (pintype "passive"))
    )
    (net (code "83") (name "Net-(D21-PadA)") (class "Default")
      (node (ref "D21") (pin "A") (pinfunction "A_A") (pintype "passive"))
      (node (ref "IC3") (pin "10") (pinfunction "10_10") (pintype "passive"))
    )
    (net (code "84") (name "Net-(D22-PadA)") (class "Default")
      (node (ref "D22") (pin "A") (pinfunction "A_A") (pintype "passive"))
      (node (ref "IC3") (pin "9") (pinfunction "9_9") (pintype "passive"))
    )
    (net (code "85") (name "Net-(D23-PadA)") (class "Default")
      (node (ref "D23") (pin "A") (pinfunction "A_A") (pintype "passive"))
      (node (ref "IC3") (pin "8") (pinfunction "8_8") (pintype "passive"))
    )
    (net (code "86") (name "Net-(D24-PadA)") (class "Default")
      (node (ref "D24") (pin "A") (pinfunction "A_A") (pintype "passive"))
      (node (ref "IC3") (pin "7") (pinfunction "7_7") (pintype "passive"))
    )
    (net (code "87") (name "Net-(IC2A-CV)") (class "Default")
      (node (ref "C4") (pin "1") (pinfunction "1_1") (pintype "passive"))
      (node (ref "IC2") (pin "3") (pinfunction "CV_3") (pintype "input"))
    )
    (net (code "88") (name "Net-(IC2A-DIS)") (class "Default")
      (node (ref "C5") (pin "1") (pinfunction "1_1") (pintype "passive"))
      (node (ref "IC2") (pin "1") (pinfunction "DIS_1") (pintype "input"))
      (node (ref "IC2") (pin "2") (pinfunction "THR_2") (pintype "input"))
      (node (ref "R19") (pin "1") (pinfunction "1_1") (pintype "passive"))
    )
    (net (code "89") (name "Net-(IC2B-THR)") (class "Default")
      (node (ref "IC2") (pin "12") (pinfunction "THR_12") (pintype "input"))
      (node (ref "R14") (pin "1") (pinfunction "1_1") (pintype "passive"))
      (node (ref "R17") (pin "2") (pinfunction "2_2") (pintype "passive"))
    )
    (net (code "90") (name "Net-(IC2B-TR)") (class "Default")
      (node (ref "IC2") (pin "8") (pinfunction "TR_8") (pintype "input"))
      (node (ref "R15") (pin "2") (pinfunction "2_2") (pintype "passive"))
      (node (ref "R16") (pin "1") (pinfunction "1_1") (pintype "passive"))
    )
    (net (code "91") (name "Net-(IC4A-A14)") (class "Default")
      (node (ref "IC4") (pin "27") (pinfunction "A14_27") (pintype "input"))
      (node (ref "ROMSEL") (pin "2") (pinfunction "2_2") (pintype "passive"))
    )
    (net (code "92") (name "Net-(IC7A-B2)") (class "Default")
      (node (ref "IC7") (pin "17") (pinfunction "B2_17") (pintype "bidirectional"))
      (node (ref "U2") (pin "27") (pinfunction "D6_27") (pintype "bidirectional"))
    )
    (net (code "93") (name "Net-(IC7A-B3)") (class "Default")
      (node (ref "IC7") (pin "16") (pinfunction "B3_16") (pintype "bidirectional"))
      (node (ref "U2") (pin "28") (pinfunction "D5_28") (pintype "bidirectional"))
    )
    (net (code "94") (name "Net-(IC7A-B4)") (class "Default")
      (node (ref "IC7") (pin "15") (pinfunction "B4_15") (pintype "bidirectional"))
      (node (ref "U2") (pin "29") (pinfunction "D4_29") (pintype "bidirectional"))
    )
    (net (code "95") (name "Net-(IC7A-B5)") (class "Default")
      (node (ref "IC7") (pin "14") (pinfunction "B5_14") (pintype "bidirectional"))
      (node (ref "U2") (pin "30") (pinfunction "D3_30") (pintype "bidirectional"))
    )
    (net (code "96") (name "Net-(IC7A-B6)") (class "Default")
      (node (ref "IC7") (pin "13") (pinfunction "B6_13") (pintype "bidirectional"))
      (node (ref "U2") (pin "31") (pinfunction "D2_31") (pintype "bidirectional"))
    )
    (net (code "97") (name "Net-(IC7A-B7)") (class "Default")
      (node (ref "IC7") (pin "12") (pinfunction "B7_12") (pintype "bidirectional"))
      (node (ref "U2") (pin "32") (pinfunction "D1_32") (pintype "bidirectional"))
    )
    (net (code "98") (name "Net-(IC8A-QH)") (class "Default")
      (node (ref "D6") (pin "C") (pinfunction "C_C") (pintype "passive"))
      (node (ref "IC8") (pin "9") (pinfunction "QH_9") (pintype "output"))
    )
    (net (code "99") (name "Net-(IC8A-SH{slash}~{LD})") (class "Default")
      (node (ref "C1") (pin "2") (pinfunction "2_2") (pintype "passive"))
      (node (ref "IC8") (pin "1") (pinfunction "SH/~{LD}_1") (pintype "input"))
      (node (ref "R5") (pin "1") (pinfunction "1_1") (pintype "passive"))
      (node (ref "R6") (pin "2") (pinfunction "2_2") (pintype "passive"))
    )
    (net (code "100") (name "Net-(IC10A-1B)") (class "Default")
      (node (ref "IC10") (pin "3") (pinfunction "1B_3") (pintype "input"))
      (node (ref "IC19") (pin "11") (pinfunction "QA_11") (pintype "output"))
    )
    (net (code "101") (name "Net-(IC10A-2B)") (class "Default")
      (node (ref "IC10") (pin "6") (pinfunction "2B_6") (pintype "input"))
      (node (ref "IC18") (pin "5") (pinfunction "QC_5") (pintype "output"))
    )
    (net (code "102") (name "Net-(IC10A-3B)") (class "Default")
      (node (ref "IC10") (pin "10") (pinfunction "3B_10") (pintype "input"))
      (node (ref "IC18") (pin "3") (pinfunction "QA_3") (pintype "output"))
      (node (ref "IC20") (pin "13") (pinfunction "B_13") (pintype "input"))
    )
    (net (code "103") (name "Net-(IC10A-4B)") (class "Default")
      (node (ref "IC10") (pin "13") (pinfunction "4B_13") (pintype "input"))
      (node (ref "IC18") (pin "6") (pinfunction "QD_6") (pintype "output"))
      (node (ref "IC19") (pin "13") (pinfunction "A_13") (pintype "input"))
    )
    (net (code "104") (name "Net-(IC13A-1A)") (class "Default")
      (node (ref "IC13") (pin "2") (pinfunction "1A_2") (pintype "input"))
      (node (ref "IC3") (pin "1") (pinfunction "1_1") (pintype "passive"))
      (node (ref "R34") (pin "2") (pinfunction "2_2") (pintype "passive"))
      (node (ref "R43") (pin "1") (pinfunction "1_1") (pintype "passive"))
    )
    (net (code "105") (name "Net-(IC13A-1B)") (class "Default")
      (node (ref "IC13") (pin "3") (pinfunction "1B_3") (pintype "input"))
      (node (ref "IC2") (pin "5") (pinfunction "Q_5") (pintype "output"))
    )
    (net (code "106") (name "Net-(IC13A-2A)") (class "Default")
      (node (ref "IC13") (pin "5") (pinfunction "2A_5") (pintype "input"))
      (node (ref "IC3") (pin "4") (pinfunction "4_4") (pintype "passive"))
      (node (ref "R35") (pin "2") (pinfunction "2_2") (pintype "passive"))
    )
    (net (code "107") (name "Net-(IC13A-2B)") (class "Default")
      (node (ref "IC13") (pin "6") (pinfunction "2B_6") (pintype "input"))
      (node (ref "IC2") (pin "9") (pinfunction "Q_9") (pintype "output"))
    )
    (net (code "108") (name "Net-(IC13A-3A)") (class "Default")
      (node (ref "IC13") (pin "11") (pinfunction "3A_11") (pintype "input"))
      (node (ref "IC3") (pin "5") (pinfunction "5_5") (pintype "passive"))
      (node (ref "R36") (pin "2") (pinfunction "2_2") (pintype "passive"))
    )
    (net (code "109") (name "Net-(IC13A-3B)") (class "Default")
      (node (ref "IC13") (pin "10") (pinfunction "3B_10") (pintype "input"))
      (node (ref "IC3") (pin "6") (pinfunction "6_6") (pintype "passive"))
      (node (ref "R37") (pin "2") (pinfunction "2_2") (pintype "passive"))
    )
    (net (code "110") (name "Net-(IC13A-4A)") (class "Default")
      (node (ref "IC13") (pin "14") (pinfunction "4A_14") (pintype "input"))
      (node (ref "IC3") (pin "2") (pinfunction "2_2") (pintype "passive"))
      (node (ref "R38") (pin "2") (pinfunction "2_2") (pintype "passive"))
    )
    (net (code "111") (name "Net-(IC13A-4B)") (class "Default")
      (node (ref "IC13") (pin "13") (pinfunction "4B_13") (pintype "input"))
      (node (ref "IC3") (pin "3") (pinfunction "3_3") (pintype "passive"))
      (node (ref "R39") (pin "2") (pinfunction "2_2") (pintype "passive"))
    )
    (net (code "112") (name "Net-(IC14B-O)") (class "Default")
      (node (ref "IC14") (pin "4") (pinfunction "O_4") (pintype "output"))
      (node (ref "IC22") (pin "14") (pinfunction "CLR_14") (pintype "input"))
    )
    (net (code "113") (name "Net-(IC14C-I)") (class "Default")
      (node (ref "C1") (pin "1") (pinfunction "1_1") (pintype "passive"))
      (node (ref "IC14") (pin "5") (pinfunction "I_5") (pintype "input"))
      (node (ref "IC22") (pin "6") (pinfunction "QC_6") (pintype "output"))
    )
    (net (code "114") (name "Net-(IC14D-I)") (class "Default")
      (node (ref "IC14") (pin "9") (pinfunction "I_9") (pintype "input"))
      (node (ref "IC20") (pin "7") (pinfunction "Y3_7") (pintype "output"))
    )
    (net (code "115") (name "Net-(IC14D-O)") (class "Default")
      (node (ref "D1") (pin "C") (pinfunction "C_C") (pintype "passive"))
      (node (ref "IC14") (pin "8") (pinfunction "O_8") (pintype "output"))
    )
    (net (code "116") (name "Net-(IC14E-I)") (class "Default")
      (node (ref "C6") (pin "2") (pinfunction "2_2") (pintype "passive"))
      (node (ref "IC14") (pin "11") (pinfunction "I_11") (pintype "input"))
      (node (ref "R21") (pin "1") (pinfunction "1_1") (pintype "passive"))
    )
    (net (code "117") (name "Net-(IC14F-I)") (class "Default")
      (node (ref "IC14") (pin "13") (pinfunction "I_13") (pintype "input"))
      (node (ref "Q1") (pin "1") (pinfunction "1_1") (pintype "passive"))
      (node (ref "R20") (pin "2") (pinfunction "2_2") (pintype "passive"))
    )
    (net (code "118") (name "Net-(IC14F-O)") (class "Default")
      (node (ref "C6") (pin "1") (pinfunction "1_1") (pintype "passive"))
      (node (ref "IC14") (pin "12") (pinfunction "O_12") (pintype "output"))
      (node (ref "R20") (pin "1") (pinfunction "1_1") (pintype "passive"))
    )
    (net (code "119") (name "Net-(IC16A-1B)") (class "Default")
      (node (ref "IC16") (pin "3") (pinfunction "1B_3") (pintype "input"))
      (node (ref "IC19") (pin "3") (pinfunction "QA_3") (pintype "output"))
    )
    (net (code "120") (name "Net-(IC16A-2B)") (class "Default")
      (node (ref "D13") (pin "C") (pinfunction "C_C") (pintype "passive"))
      (node (ref "IC16") (pin "6") (pinfunction "2B_6") (pintype "input"))
      (node (ref "IC19") (pin "9") (pinfunction "QC_9") (pintype "output"))
    )
    (net (code "121") (name "Net-(IC16A-3B)") (class "Default")
      (node (ref "D4") (pin "C") (pinfunction "C_C") (pintype "passive"))
      (node (ref "IC16") (pin "10") (pinfunction "3B_10") (pintype "input"))
      (node (ref "IC19") (pin "10") (pinfunction "QB_10") (pintype "output"))
    )
    (net (code "122") (name "Net-(IC16A-4B)") (class "Default")
      (node (ref "IC16") (pin "13") (pinfunction "4B_13") (pintype "input"))
      (node (ref "IC19") (pin "1") (pinfunction "A_1") (pintype "input"))
      (node (ref "IC19") (pin "8") (pinfunction "QD_8") (pintype "output"))
      (node (ref "IC20") (pin "3") (pinfunction "B_3") (pintype "input"))
    )
    (net (code "123") (name "Net-(IC17A-3B)") (class "Default")
      (node (ref "IC17") (pin "10") (pinfunction "3B_10") (pintype "input"))
      (node (ref "IC19") (pin "4") (pinfunction "QB_4") (pintype "output"))
    )
    (net (code "124") (name "Net-(IC18A-A)") (class "Default")
      (node (ref "D2") (pin "C") (pinfunction "C_C") (pintype "passive"))
      (node (ref "IC18") (pin "1") (pinfunction "A_1") (pintype "input"))
      (node (ref "IC18") (pin "8") (pinfunction "QD_8") (pintype "output"))
      (node (ref "IC9") (pin "3") (pinfunction "1B_3") (pintype "input"))
    )
    (net (code "125") (name "Net-(IC18A-CLR)") (class "Default")
      (node (ref "D1") (pin "A") (pinfunction "A_A") (pintype "passive"))
      (node (ref "D4") (pin "A") (pinfunction "A_A") (pintype "passive"))
      (node (ref "IC18") (pin "12") (pinfunction "CLR_12") (pintype "input"))
      (node (ref "IC18") (pin "2") (pinfunction "CLR_2") (pintype "input"))
      (node (ref "IC19") (pin "12") (pinfunction "CLR_12") (pintype "input"))
      (node (ref "IC19") (pin "2") (pinfunction "CLR_2") (pintype "input"))
      (node (ref "R3") (pin "2") (pinfunction "2_2") (pintype "passive"))
    )
    (net (code "126") (name "Net-(IC18A-QB)") (class "Default")
      (node (ref "IC18") (pin "4") (pinfunction "QB_4") (pintype "output"))
      (node (ref "IC21") (pin "12") (pinfunction "D_12") (pintype "input"))
    )
    (net (code "127") (name "Net-(IC18B-QA)") (class "Default")
      (node (ref "IC18") (pin "11") (pinfunction "QA_11") (pintype "output"))
      (node (ref "IC9") (pin "10") (pinfunction "3B_10") (pintype "input"))
    )
    (net (code "128") (name "Net-(IC18B-QB)") (class "Default")
      (node (ref "IC18") (pin "10") (pinfunction "QB_10") (pintype "output"))
      (node (ref "IC9") (pin "6") (pinfunction "2B_6") (pintype "input"))
    )
    (net (code "129") (name "Net-(IC18B-QC)") (class "Default")
      (node (ref "D3") (pin "C") (pinfunction "C_C") (pintype "passive"))
      (node (ref "IC18") (pin "9") (pinfunction "QC_9") (pintype "output"))
      (node (ref "IC9") (pin "13") (pinfunction "4B_13") (pintype "input"))
    )
    (net (code "130") (name "Net-(IC19A-QC)") (class "Default")
      (node (ref "D5") (pin "C") (pinfunction "C_C") (pintype "passive"))
      (node (ref "IC19") (pin "5") (pinfunction "QC_5") (pintype "output"))
      (node (ref "IC21") (pin "2") (pinfunction "D_2") (pintype "input"))
      (node (ref "R4") (pin "2") (pinfunction "2_2") (pintype "passive"))
    )
    (net (code "131") (name "Net-(IC20A-A)") (class "Default")
      (node (ref "D13") (pin "A") (pinfunction "A_A") (pintype "passive"))
      (node (ref "D5") (pin "A") (pinfunction "A_A") (pintype "passive"))
      (node (ref "IC20") (pin "2") (pinfunction "A_2") (pintype "input"))
      (node (ref "R22") (pin "1") (pinfunction "1_1") (pintype "passive"))
    )
    (net (code "132") (name "Net-(IC20B-A)") (class "Default")
      (node (ref "D2") (pin "A") (pinfunction "A_A") (pintype "passive"))
      (node (ref "D3") (pin "A") (pinfunction "A_A") (pintype "passive"))
      (node (ref "IC20") (pin "14") (pinfunction "A_14") (pintype "input"))
      (node (ref "R2") (pin "2") (pinfunction "2_2") (pintype "passive"))
    )
    (net (code "133") (name "Net-(IC21A-CLR)") (class "Default")
      (node (ref "IC21") (pin "1") (pinfunction "CLR_1") (pintype "input"))
      (node (ref "IC21") (pin "10") (pinfunction "PRE_10") (pintype "input"))
      (node (ref "IC21") (pin "13") (pinfunction "CLR_13") (pintype "input"))
      (node (ref "IC21") (pin "4") (pinfunction "PRE_4") (pintype "input"))
      (node (ref "R26") (pin "2") (pinfunction "2_2") (pintype "passive"))
    )
    (net (code "134") (name "Net-(IC22A-B)") (class "Default")
      (node (ref "IC22") (pin "3") (pinfunction "QA_3") (pintype "output"))
      (node (ref "IC22") (pin "4") (pinfunction "B_4") (pintype "input"))
    )
    (net (code "135") (name "Net-(IC22A-CLR)") (class "Default")
      (node (ref "IC22") (pin "2") (pinfunction "CLR_2") (pintype "input"))
      (node (ref "IC22") (pin "7") (pinfunction "QD_7") (pintype "output"))
    )
    (net (code "136") (name "Net-(IC22B-QA)") (class "Default")
      (node (ref "IC22") (pin "13") (pinfunction "QA_13") (pintype "output"))
      (node (ref "R10") (pin "1") (pinfunction "1_1") (pintype "passive"))
      (node (ref "R29") (pin "2") (pinfunction "2_2") (pintype "passive"))
    )
    (net (code "137") (name "Net-(IC22B-QB)") (class "Default")
      (node (ref "IC22") (pin "11") (pinfunction "QB_11") (pintype "output"))
      (node (ref "R40") (pin "1") (pinfunction "1_1") (pintype "passive"))
      (node (ref "R44") (pin "1") (pinfunction "1_1") (pintype "passive"))
    )
    (net (code "138") (name "Net-(JP1-Pad4)") (class "Default")
      (node (ref "JP1") (pin "4") (pinfunction "4_4") (pintype "passive"))
      (node (ref "R19") (pin "2") (pinfunction "2_2") (pintype "passive"))
    )
    (net (code "139") (name "Net-(JP1-Pad5)") (class "Default")
      (node (ref "JP1") (pin "5") (pinfunction "5_5") (pintype "passive"))
      (node (ref "R18") (pin "2") (pinfunction "2_2") (pintype "passive"))
    )
    (net (code "140") (name "Net-(JP3-Pad1)") (class "Default")
      (node (ref "JP3") (pin "1") (pinfunction "1_1") (pintype "passive"))
      (node (ref "R42") (pin "1") (pinfunction "1_1") (pintype "passive"))
    )
    (net (code "141") (name "Net-(JP3-Pad3)") (class "Default")
      (node (ref "JP3") (pin "3") (pinfunction "3_3") (pintype "passive"))
      (node (ref "R43") (pin "2") (pinfunction "2_2") (pintype "passive"))
    )
    (net (code "142") (name "Net-(R45-Pad2)") (class "Default")
      (node (ref "R45") (pin "2") (pinfunction "2_2") (pintype "passive"))
      (node (ref "VIDEO_OUT") (pin "1") (pinfunction "1_1") (pintype "passive"))
    )
    (net (code "143") (name "Net-(T1-B)") (class "Default")
      (node (ref "R29") (pin "1") (pinfunction "1_1") (pintype "passive"))
      (node (ref "T1") (pin "2") (pinfunction "B_2") (pintype "passive"))
    )
    (net (code "144") (name "Net-(T1-E)") (class "Default")
      (node (ref "R12") (pin "1") (pinfunction "1_1") (pintype "passive"))
      (node (ref "T1") (pin "1") (pinfunction "E_1") (pintype "passive"))
    )
    (net (code "145") (name "Net-(T2-B)") (class "Default")
      (node (ref "R40") (pin "2") (pinfunction "2_2") (pintype "passive"))
      (node (ref "T2") (pin "2") (pinfunction "B_2") (pintype "passive"))
    )
    (net (code "146") (name "Net-(T2-C)") (class "Default")
      (node (ref "R41") (pin "1") (pinfunction "1_1") (pintype "passive"))
      (node (ref "R42") (pin "2") (pinfunction "2_2") (pintype "passive"))
      (node (ref "T2") (pin "3") (pinfunction "C_3") (pintype "passive"))
    )
    (net (code "147") (name "Net-(T3-B)") (class "Default")
      (node (ref "D10") (pin "A") (pinfunction "A_A") (pintype "passive"))
      (node (ref "D9") (pin "A") (pinfunction "A_A") (pintype "passive"))
      (node (ref "R7") (pin "2") (pinfunction "2_2") (pintype "passive"))
      (node (ref "R8") (pin "1") (pinfunction "1_1") (pintype "passive"))
      (node (ref "R9") (pin "1") (pinfunction "1_1") (pintype "passive"))
      (node (ref "T3") (pin "2") (pinfunction "B_2") (pintype "passive"))
    )
    (net (code "148") (name "Net-(T3-E)") (class "Default")
      (node (ref "R45") (pin "1") (pinfunction "1_1") (pintype "passive"))
      (node (ref "T3") (pin "1") (pinfunction "E_1") (pintype "passive"))
    )
    (net (code "149") (name "Net-(U2-SOB)") (class "Default")
      (node (ref "R23") (pin "2") (pinfunction "2_2") (pintype "passive"))
      (node (ref "U2") (pin "38") (pinfunction "SOB_38") (pintype "input"))
    )
    (net (code "150") (name "VCC") (class "Default")
      (node (ref "CD1") (pin "2") (pinfunction "2_2") (pintype "passive"))
      (node (ref "CD10") (pin "2") (pinfunction "2_2") (pintype "passive"))
      (node (ref "CD11") (pin "2") (pinfunction "2_2") (pintype "passive"))
      (node (ref "CD12") (pin "2") (pinfunction "2_2") (pintype "passive"))
      (node (ref "CD13") (pin "2") (pinfunction "2_2") (pintype "passive"))
      (node (ref "CD14") (pin "2") (pinfunction "2_2") (pintype "passive"))
      (node (ref "CD15") (pin "2") (pinfunction "2_2") (pintype "passive"))
      (node (ref "CD2") (pin "2") (pinfunction "2_2") (pintype "passive"))
      (node (ref "CD3") (pin "2") (pinfunction "2_2") (pintype "passive"))
      (node (ref "CD4") (pin "2") (pinfunction "2_2") (pintype "passive"))
      (node (ref "CD5") (pin "2") (pinfunction "2_2") (pintype "passive"))
      (node (ref "CD6") (pin "2") (pinfunction "2_2") (pintype "passive"))
      (node (ref "CD7") (pin "2") (pinfunction "2_2") (pintype "passive"))
      (node (ref "CD8") (pin "2") (pinfunction "2_2") (pintype "passive"))
      (node (ref "CD9") (pin "2") (pinfunction "2_2") (pintype "passive"))
      (node (ref "IC17") (pin "13") (pinfunction "4B_13") (pintype "input"))
      (node (ref "IC17") (pin "6") (pinfunction "2B_6") (pintype "input"))
      (node (ref "IC2") (pin "10") (pinfunction "R_10") (pintype "input"))
      (node (ref "IC2") (pin "14") (pinfunction "V+_14") (pintype "power_in"))
      (node (ref "IC2") (pin "4") (pinfunction "R_4") (pintype "input"))
      (node (ref "IC26") (pin "28") (pinfunction "VCC_28") (pintype "power_in"))
      (node (ref "IC4") (pin "1") (pinfunction "VPP_1") (pintype "input"))
      (node (ref "JP2") (pin "1") (pinfunction "1_1") (pintype "passive"))
      (node (ref "PWR") (pin "1") (pinfunction "1_1") (pintype "passive"))
      (node (ref "R18") (pin "1") (pinfunction "1_1") (pintype "passive"))
      (node (ref "R2") (pin "1") (pinfunction "1_1") (pintype "passive"))
      (node (ref "R22") (pin "2") (pinfunction "2_2") (pintype "passive"))
      (node (ref "R23") (pin "1") (pinfunction "1_1") (pintype "passive"))
      (node (ref "R24") (pin "1") (pinfunction "1_1") (pintype "passive"))
      (node (ref "R25") (pin "2") (pinfunction "2_2") (pintype "passive"))
      (node (ref "R26") (pin "1") (pinfunction "1_1") (pintype "passive"))
      (node (ref "R27") (pin "2") (pinfunction "2_2") (pintype "passive"))
      (node (ref "R3") (pin "1") (pinfunction "1_1") (pintype "passive"))
      (node (ref "R31") (pin "1") (pinfunction "1_1") (pintype "passive"))
      (node (ref "R32") (pin "1") (pinfunction "1_1") (pintype "passive"))
      (node (ref "R33") (pin "1") (pinfunction "1_1") (pintype "passive"))
      (node (ref "R34") (pin "1") (pinfunction "1_1") (pintype "passive"))
      (node (ref "R35") (pin "1") (pinfunction "1_1") (pintype "passive"))
      (node (ref "R36") (pin "1") (pinfunction "1_1") (pintype "passive"))
      (node (ref "R37") (pin "1") (pinfunction "1_1") (pintype "passive"))
      (node (ref "R38") (pin "1") (pinfunction "1_1") (pintype "passive"))
      (node (ref "R39") (pin "1") (pinfunction "1_1") (pintype "passive"))
      (node (ref "R44") (pin "2") (pinfunction "2_2") (pintype "passive"))
      (node (ref "R5") (pin "2") (pinfunction "2_2") (pintype "passive"))
      (node (ref "R8") (pin "2") (pinfunction "2_2") (pintype "passive"))
      (node (ref "ROMSEL") (pin "1") (pinfunction "1_1") (pintype "passive"))
      (node (ref "T1") (pin "3") (pinfunction "C_3") (pintype "passive"))
      (node (ref "T2") (pin "1") (pinfunction "E_1") (pintype "passive"))
      (node (ref "T3") (pin "3") (pinfunction "C_3") (pintype "passive"))
      (node (ref "U2") (pin "8") (pinfunction "VDD_8") (pintype "power_in"))
    )
    (net (code "151") (name "unconnected-(IC2B-CV-Pad11)") (class "Default")
      (node (ref "IC2") (pin "11") (pinfunction "CV_11") (pintype "input"))
    )
    (net (code "152") (name "unconnected-(IC2B-DIS-Pad13)") (class "Default")
      (node (ref "IC2") (pin "13") (pinfunction "DIS_13") (pintype "input"))
    )
    (net (code "153") (name "unconnected-(IC8A-~{QH}-Pad7)") (class "Default")
      (node (ref "IC8") (pin "7") (pinfunction "~{QH}_7") (pintype "output"))
    )
    (net (code "154") (name "unconnected-(IC19A-QD-Pad6)") (class "Default")
      (node (ref "IC19") (pin "6") (pinfunction "QD_6") (pintype "output"))
    )
    (net (code "155") (name "unconnected-(IC20A-Y0-Pad4)") (class "Default")
      (node (ref "IC20") (pin "4") (pinfunction "Y0_4") (pintype "output"))
    )
    (net (code "156") (name "unconnected-(IC20A-Y2-Pad6)") (class "Default")
      (node (ref "IC20") (pin "6") (pinfunction "Y2_6") (pintype "output"))
    )
    (net (code "157") (name "unconnected-(IC20B-Y0-Pad12)") (class "Default")
      (node (ref "IC20") (pin "12") (pinfunction "Y0_12") (pintype "output"))
    )
    (net (code "158") (name "unconnected-(IC20B-Y2-Pad10)") (class "Default")
      (node (ref "IC20") (pin "10") (pinfunction "Y2_10") (pintype "output"))
    )
    (net (code "159") (name "unconnected-(IC20B-Y3-Pad9)") (class "Default")
      (node (ref "IC20") (pin "9") (pinfunction "Y3_9") (pintype "output"))
    )
    (net (code "160") (name "unconnected-(IC21A-Q-Pad5)") (class "Default")
      (node (ref "IC21") (pin "5") (pinfunction "Q_5") (pintype "output"))
    )
    (net (code "161") (name "unconnected-(IC21B-~{Q}-Pad8)") (class "Default")
      (node (ref "IC21") (pin "8") (pinfunction "~{Q}_8") (pintype "output"))
    )
    (net (code "162") (name "unconnected-(IC22B-QC-Pad10)") (class "Default")
      (node (ref "IC22") (pin "10") (pinfunction "QC_10") (pintype "output"))
    )
    (net (code "163") (name "unconnected-(IC22B-QD-Pad9)") (class "Default")
      (node (ref "IC22") (pin "9") (pinfunction "QD_9") (pintype "output"))
    )
    (net (code "164") (name "unconnected-(U2-NC$1-Pad5)") (class "Default")
      (node (ref "U2") (pin "5") (pinfunction "NC$1_5") (pintype "no_connect"))
    )
    (net (code "165") (name "unconnected-(U2-NC$2-Pad35)") (class "Default")
      (node (ref "U2") (pin "35") (pinfunction "NC$2_35") (pintype "no_connect"))
    )
    (net (code "166") (name "unconnected-(U2-NC$3-Pad36)") (class "Default")
      (node (ref "U2") (pin "36") (pinfunction "NC$3_36") (pintype "no_connect"))
    )
    (net (code "167") (name "unconnected-(U2-PHI1-Pad3)") (class "Default")
      (node (ref "U2") (pin "3") (pinfunction "PHI1_3") (pintype "output"))
    )
  )
)
